# SO-8-minimal.net
KiCad netlist of a schematic drawn in EAGLE
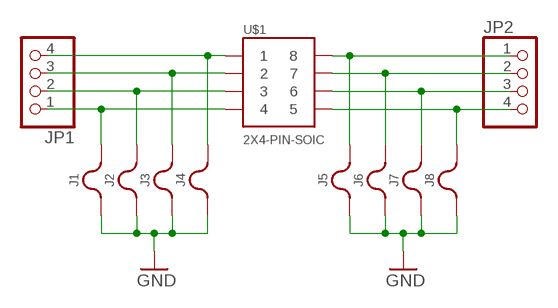
[diagram p0: schematic, sheet 1]

(export (version "E")
  (design (tool "Eeschema 10.0.6"))
  (components
    (comp (ref "J1")
      (value "JUMPER-0805")
      (footprint "eagle-import:RCLJ-0805")
      (libsource (lib "eagle-import") (part "JUMPER-0805"))
    )
    (comp (ref "J2")
      (value "JUMPER-0805")
      (footprint "eagle-import:RCLJ-0805")
      (libsource (lib "eagle-import") (part "JUMPER-0805"))
    )
    (comp (ref "J3")
      (value "JUMPER-0805")
      (footprint "eagle-import:RCLJ-0805")
      (libsource (lib "eagle-import") (part "JUMPER-0805"))
    )
    (comp (ref "J4")
      (value "JUMPER-0805")
      (footprint "eagle-import:RCLJ-0805")
      (libsource (lib "eagle-import") (part "JUMPER-0805"))
    )
    (comp (ref "J5")
      (value "JUMPER-0805")
      (footprint "eagle-import:RCLJ-0805")
      (libsource (lib "eagle-import") (part "JUMPER-0805"))
    )
    (comp (ref "J6")
      (value "JUMPER-0805")
      (footprint "eagle-import:RCLJ-0805")
      (libsource (lib "eagle-import") (part "JUMPER-0805"))
    )
    (comp (ref "J7")
      (value "JUMPER-0805")
      (footprint "eagle-import:RCLJ-0805")
      (libsource (lib "eagle-import") (part "JUMPER-0805"))
    )
    (comp (ref "J8")
      (value "JUMPER-0805")
      (footprint "eagle-import:RCLJ-0805")
      (libsource (lib "eagle-import") (part "JUMPER-0805"))
    )
    (comp (ref "JP1")
      (value "PINHD-1X4")
      (footprint "eagle-import:1X04")
      (libsource (lib "eagle-import") (part "PINHD-1X4"))
    )
    (comp (ref "JP2")
      (value "PINHD-1X4")
      (footprint "eagle-import:1X04")
      (libsource (lib "eagle-import") (part "PINHD-1X4"))
    )
    (comp (ref "U$1")
      (value "2X4-PIN-SOIC")
      (footprint "eagle-import:SO8")
      (libsource (lib "eagle-import") (part "2X4-PIN-SOIC"))
    )
  )
  (nets
    (net (code "1") (name "GND") (class "Default")
      (node (ref "J1") (pin "1") (pinfunction "P$1_1") (pintype "bidirectional"))
      (node (ref "J2") (pin "1") (pinfunction "P$1_1") (pintype "bidirectional"))
      (node (ref "J3") (pin "1") (pinfunction "P$1_1") (pintype "bidirectional"))
      (node (ref "J4") (pin "1") (pinfunction "P$1_1") (pintype "bidirectional"))
      (node (ref "J5") (pin "1") (pinfunction "P$1_1") (pintype "bidirectional"))
      (node (ref "J6") (pin "1") (pinfunction "P$1_1") (pintype "bidirectional"))
      (node (ref "J7") (pin "1") (pinfunction "P$1_1") (pintype "bidirectional"))
      (node (ref "J8") (pin "1") (pinfunction "P$1_1") (pintype "bidirectional"))
    )
    (net (code "2") (name "Net-(J1-P$2)") (class "Default")
      (node (ref "J1") (pin "2") (pinfunction "P$2_2") (pintype "bidirectional"))
      (node (ref "JP1") (pin "1") (pinfunction "1_1") (pintype "passive"))
      (node (ref "U$1") (pin "P$4") (pinfunction "4_P$4") (pintype "bidirectional"))
    )
    (net (code "3") (name "Net-(J2-P$2)") (class "Default")
      (node (ref "J2") (pin "2") (pinfunction "P$2_2") (pintype "bidirectional"))
      (node (ref "JP1") (pin "2") (pinfunction "2_2") (pintype "passive"))
      (node (ref "U$1") (pin "P$3") (pinfunction "3_P$3") (pintype "bidirectional"))
    )
    (net (code "4") (name "Net-(J3-P$2)") (class "Default")
      (node (ref "J3") (pin "2") (pinfunction "P$2_2") (pintype "bidirectional"))
      (node (ref "JP1") (pin "3") (pinfunction "3_3") (pintype "passive"))
      (node (ref "U$1") (pin "P$2") (pinfunction "2_P$2") (pintype "bidirectional"))
    )
    (net (code "5") (name "Net-(J4-P$2)") (class "Default")
      (node (ref "J4") (pin "2") (pinfunction "P$2_2") (pintype "bidirectional"))
      (node (ref "JP1") (pin "4") (pinfunction "4_4") (pintype "passive"))
      (node (ref "U$1") (pin "P$1") (pinfunction "1_P$1") (pintype "bidirectional"))
    )
    (net (code "6") (name "Net-(J5-P$2)") (class "Default")
      (node (ref "J5") (pin "2") (pinfunction "P$2_2") (pintype "bidirectional"))
      (node (ref "JP2") (pin "1") (pinfunction "1_1") (pintype "passive"))
      (node (ref "U$1") (pin "P$8") (pinfunction "8_P$8") (pintype "bidirectional"))
    )
    (net (code "7") (name "Net-(J6-P$2)") (class "Default")
      (node (ref "J6") (pin "2") (pinfunction "P$2_2") (pintype "bidirectional"))
      (node (ref "JP2") (pin "2") (pinfunction "2_2") (pintype "passive"))
      (node (ref "U$1") (pin "P$7") (pinfunction "7_P$7") (pintype "bidirectional"))
    )
    (net (code "8") (name "Net-(J7-P$2)") (class "Default")
      (node (ref "J7") (pin "2") (pinfunction "P$2_2") (pintype "bidirectional"))
      (node (ref "JP2") (pin "3") (pinfunction "3_3") (pintype "passive"))
      (node (ref "U$1") (pin "P$6") (pinfunction "6_P$6") (pintype "bidirectional"))
    )
    (net (code "9") (name "Net-(J8-P$2)") (class "Default")
      (node (ref "J8") (pin "2") (pinfunction "P$2_2") (pintype "bidirectional"))
      (node (ref "JP2") (pin "4") (pinfunction "4_4") (pintype "passive"))
      (node (ref "U$1") (pin "P$5") (pinfunction "5_P$5") (pintype "bidirectional"))
    )
  )
)
